# USB_CY7C68001-56LFC.net
KiCad netlist of a schematic drawn in Altium Designer
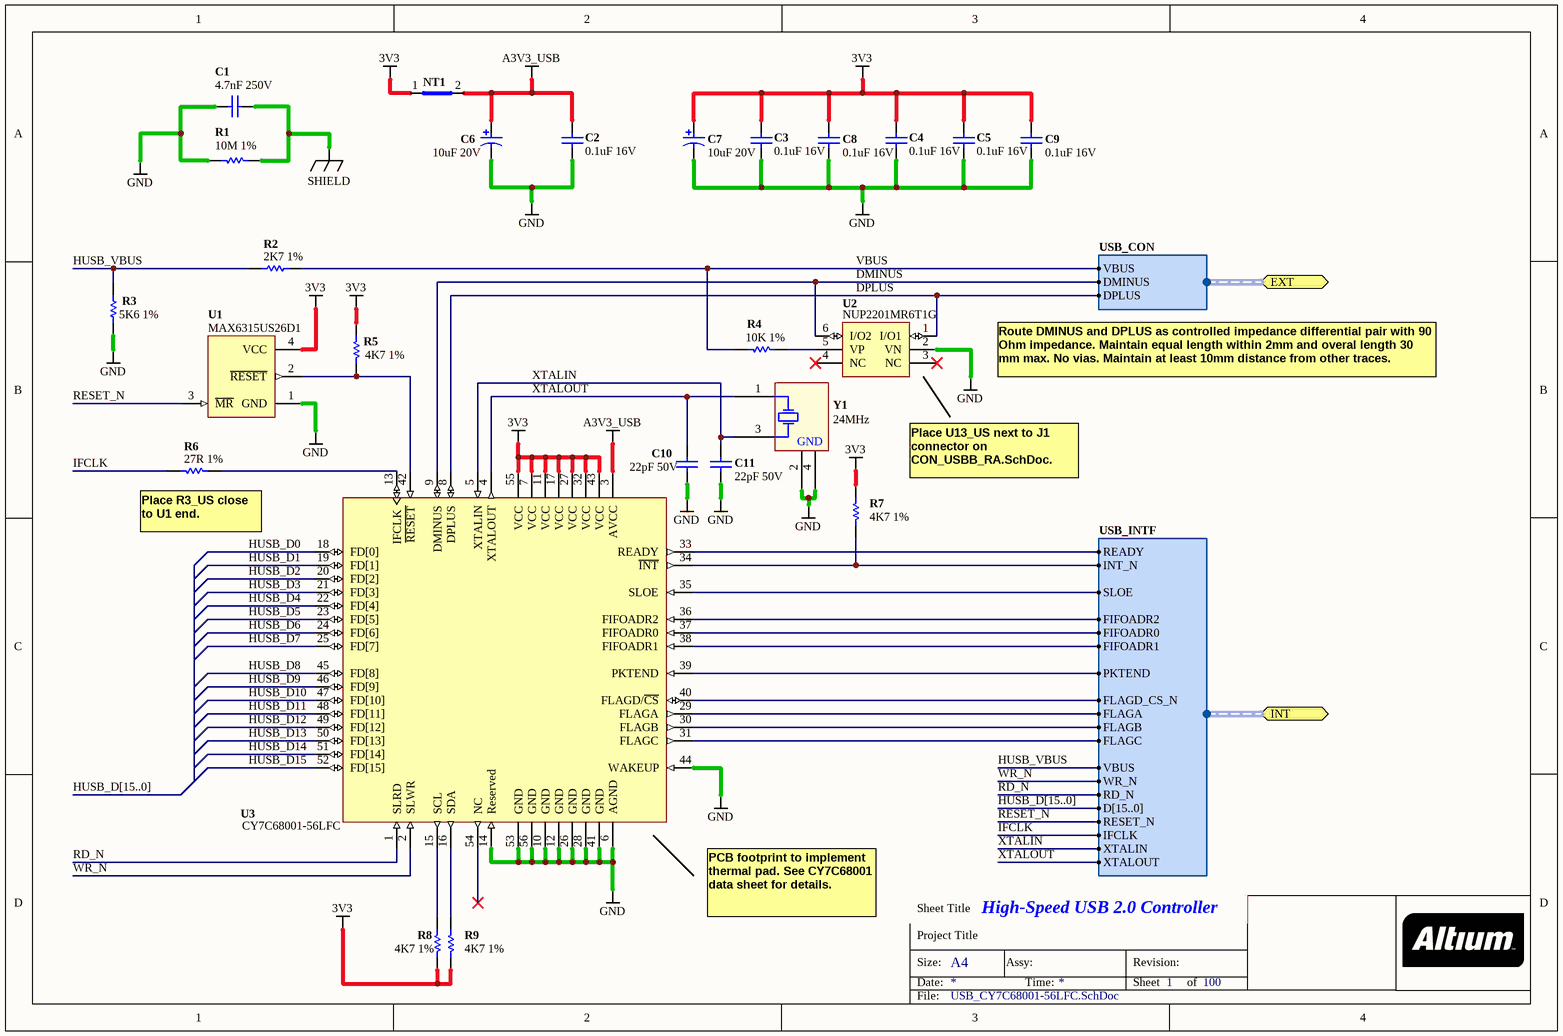
[diagram p0: USB_CY7C68001-56LFC.SchDoc]

(export (version "E")
  (design (tool "Eeschema 10.0.6"))
  (components
    (comp (ref "C1")
      (value "4.7nF 250V")
      (footprint "CAPM7163")
      (description "Capacitor, Ceramic, 4.7nF 20% 250V Panasonic BC J Lead (CAPM7163) Y5V")
      (fields (field (name "TOLERANCE") "20% %"))
      (libsource (lib "AltiumDesignLibrary") (part "CAP-NP"))
    )
    (comp (ref "C2")
      (value "0.1uF 16V")
      (footprint "CAPC1005-STAR")
      (description "Capacitor, Ceramic, 0.1uF 10% 16V 0402 (1005) X7R")
      (fields (field (name "TOLERANCE") "10 %"))
      (libsource (lib "AltiumDesignLibrary") (part "CAP-NP"))
    )
    (comp (ref "C3")
      (value "0.1uF 16V")
      (footprint "CAPC1005-STAR")
      (description "Capacitor, Ceramic, 0.1uF 10% 16V 0402 (1005) X7R")
      (fields (field (name "TOLERANCE") "10 %"))
      (libsource (lib "AltiumDesignLibrary") (part "CAP-NP"))
    )
    (comp (ref "C4")
      (value "0.1uF 16V")
      (footprint "CAPC1005-STAR")
      (description "Capacitor, Ceramic, 0.1uF 10% 16V 0402 (1005) X7R")
      (fields (field (name "TOLERANCE") "10 %"))
      (libsource (lib "AltiumDesignLibrary") (part "CAP-NP"))
    )
    (comp (ref "C5")
      (value "0.1uF 16V")
      (footprint "CAPC1005-STAR")
      (description "Capacitor, Ceramic, 0.1uF 10% 16V 0402 (1005) X7R")
      (fields (field (name "TOLERANCE") "10 %"))
      (libsource (lib "AltiumDesignLibrary") (part "CAP-NP"))
    )
    (comp (ref "C6")
      (value "10uF 20V")
      (footprint "CAPC3528-STAR")
      (description "Capacitor, Tantalum, 10uF 10% 20V MCCT-B (3528)")
      (fields (field (name "TOLERANCE") "10 %"))
      (libsource (lib "AltiumDesignLibrary") (part "CAP-P"))
    )
    (comp (ref "C7")
      (value "10uF 20V")
      (footprint "CAPC3528-STAR")
      (description "Capacitor, Tantalum, 10uF 10% 20V MCCT-B (3528)")
      (fields (field (name "TOLERANCE") "10 %"))
      (libsource (lib "AltiumDesignLibrary") (part "CAP-P"))
    )
    (comp (ref "C8")
      (value "0.1uF 16V")
      (footprint "CAPC1005-STAR")
      (description "Capacitor, Ceramic, 0.1uF 10% 16V 0402 (1005) X7R")
      (fields (field (name "TOLERANCE") "10 %"))
      (libsource (lib "AltiumDesignLibrary") (part "CAP-NP"))
    )
    (comp (ref "C9")
      (value "0.1uF 16V")
      (footprint "CAPC1005-STAR")
      (description "Capacitor, Ceramic, 0.1uF 10% 16V 0402 (1005) X7R")
      (fields (field (name "TOLERANCE") "10 %"))
      (libsource (lib "AltiumDesignLibrary") (part "CAP-NP"))
    )
    (comp (ref "C10")
      (value "22pF 50V")
      (footprint "CAPC1005-STAR")
      (description "Capacitor, Ceramic, 22pF 5% 50V 0402 (1005) COG")
      (fields (field (name "TOLERANCE") "5 %"))
      (libsource (lib "AltiumDesignLibrary") (part "CAP-NP"))
    )
    (comp (ref "C11")
      (value "22pF 50V")
      (footprint "CAPC1005-STAR")
      (description "Capacitor, Ceramic, 22pF 5% 50V 0402 (1005) COG")
      (fields (field (name "TOLERANCE") "5 %"))
      (libsource (lib "AltiumDesignLibrary") (part "CAP-NP"))
    )
    (comp (ref "NT1")
      (value "Net Tie SMT2")
      (footprint "NETTIE-SMT2-31X51")
      (description "Net-Tie, Surface Mount, 2 x 1.6mm x 0.8mm SMT Pads - For 0.8mm Track")
      (libsource (lib "AltiumDesignLibrary") (part "NETTIE-SMT2"))
    )
    (comp (ref "R1")
      (value "10M 1%")
      (footprint "RESC3216")
      (description "Resistor, 10M 1%1206 (3216)")
      (fields (field (name "TOLERANCE") "1 %"))
      (libsource (lib "AltiumDesignLibrary") (part "RES"))
    )
    (comp (ref "R2")
      (value "2K7 1%")
      (footprint "RESC1005-STAR")
      (description "Resistor, 2K7 1% 0402 (1005)")
      (fields (field (name "TOLERANCE") "1 %"))
      (libsource (lib "AltiumDesignLibrary") (part "RES"))
    )
    (comp (ref "R3")
      (value "5K6 1%")
      (footprint "RESC1005-STAR")
      (description "Resistor, 5K6 1% 0402 (1005)")
      (fields (field (name "TOLERANCE") "1 %"))
      (libsource (lib "AltiumDesignLibrary") (part "RES"))
    )
    (comp (ref "R4")
      (value "10K 1%")
      (footprint "RESC1005-STAR")
      (description "Resistor, 10K 1% 0402 (1005)")
      (fields (field (name "TOLERANCE") "1 %"))
      (libsource (lib "AltiumDesignLibrary") (part "RES"))
    )
    (comp (ref "R5")
      (value "4K7 1%")
      (footprint "RESC1005-STAR")
      (description "Resistor, 4K7 1% 0402 (1005)")
      (fields (field (name "TOLERANCE") "1 %"))
      (libsource (lib "AltiumDesignLibrary") (part "RES"))
    )
    (comp (ref "R6")
      (value "27R 1%")
      (footprint "RESC1005-STAR")
      (description "Resistor, 27R 1% 0402 (1005)")
      (fields (field (name "TOLERANCE") "1 %"))
      (libsource (lib "AltiumDesignLibrary") (part "RES"))
    )
    (comp (ref "R7")
      (value "4K7 1%")
      (footprint "RESC1005-STAR")
      (description "Resistor, 4K7 1% 0402 (1005)")
      (fields (field (name "TOLERANCE") "1 %"))
      (libsource (lib "AltiumDesignLibrary") (part "RES"))
    )
    (comp (ref "R8")
      (value "4K7 1%")
      (footprint "RESC1005-STAR")
      (description "Resistor, 4K7 1% 0402 (1005)")
      (fields (field (name "TOLERANCE") "1 %"))
      (libsource (lib "AltiumDesignLibrary") (part "RES"))
    )
    (comp (ref "R9")
      (value "4K7 1%")
      (footprint "RESC1005-STAR")
      (description "Resistor, 4K7 1% 0402 (1005)")
      (fields (field (name "TOLERANCE") "1 %"))
      (libsource (lib "AltiumDesignLibrary") (part "RES"))
    )
    (comp (ref "U1")
      (value "MAX6315US26D1")
      (footprint "SOT143")
      (description "MAX6315, Open-Drain Output SOT Reset IC, Customized Reset Thresholds, Timeout Delays")
      (libsource (lib "AltiumDesignLibrary") (part "MAX6315"))
    )
    (comp (ref "U2")
      (value "NUP2201MR6T1G")
      (footprint "TSOP95P275-6")
      (description "NUP2201MR6, Low Capacitance Diode Array, USB Protection")
      (libsource (lib "AltiumDesignLibrary") (part "NUP2201MR6"))
    )
    (comp (ref "U3")
      (value "CY7C68001-56LFC")
      (footprint "QFN50P800X800_HS-57")
      (description "CY7C68001-56LFC, EZ-USB SX2 High-Speed USB Interface")
      (libsource (lib "AltiumDesignLibrary") (part "CY7C68001-56LFC"))
    )
    (comp (ref "Y1")
      (value "24MHz")
      (footprint "XTAL-200X126-4")
      (description "Crystal, SMD, 24.000000MHz Stab=30ppm 20.0pF")
      (libsource (lib "AltiumDesignLibrary") (part "CRYSTAL-200X126-4"))
    )
  )
  (nets
    (net (code "3") (name "/DMINUS") (class "Default")
      (node (ref "U2") (pin "6") (pinfunction "I/O2_6") (pintype "bidirectional"))
      (node (ref "U3") (pin "9") (pinfunction "DMINUS_9") (pintype "bidirectional"))
    )
    (net (code "4") (name "/DPLUS") (class "Default")
      (node (ref "U2") (pin "1") (pinfunction "I/O1_1") (pintype "bidirectional"))
      (node (ref "U3") (pin "8") (pinfunction "DPLUS_8") (pintype "bidirectional"))
    )
    (net (code "5") (name "/FIFOADR0") (class "Default")
      (node (ref "U3") (pin "37") (pinfunction "FIFOADR0_37") (pintype "input"))
    )
    (net (code "6") (name "/FIFOADR1") (class "Default")
      (node (ref "U3") (pin "38") (pinfunction "FIFOADR1_38") (pintype "input"))
    )
    (net (code "7") (name "/FIFOADR2") (class "Default")
      (node (ref "U3") (pin "36") (pinfunction "FIFOADR2_36") (pintype "input"))
    )
    (net (code "8") (name "/FLAGA") (class "Default")
      (node (ref "U3") (pin "29") (pinfunction "FLAGA_29") (pintype "output"))
    )
    (net (code "9") (name "/FLAGB") (class "Default")
      (node (ref "U3") (pin "30") (pinfunction "FLAGB_30") (pintype "output"))
    )
    (net (code "10") (name "/FLAGC") (class "Default")
      (node (ref "U3") (pin "31") (pinfunction "FLAGC_31") (pintype "output"))
    )
    (net (code "11") (name "/FLAGD_CS_N") (class "Default")
      (node (ref "U3") (pin "40") (pinfunction "FLAGD/~{CS}_40") (pintype "bidirectional"))
    )
    (net (code "12") (name "/HUSB_D0") (class "Default")
      (node (ref "U3") (pin "18") (pinfunction "FD[0]_18") (pintype "bidirectional"))
    )
    (net (code "13") (name "/HUSB_D1") (class "Default")
      (node (ref "U3") (pin "19") (pinfunction "FD[1]_19") (pintype "bidirectional"))
    )
    (net (code "14") (name "/HUSB_D2") (class "Default")
      (node (ref "U3") (pin "20") (pinfunction "FD[2]_20") (pintype "bidirectional"))
    )
    (net (code "15") (name "/HUSB_D3") (class "Default")
      (node (ref "U3") (pin "21") (pinfunction "FD[3]_21") (pintype "bidirectional"))
    )
    (net (code "16") (name "/HUSB_D4") (class "Default")
      (node (ref "U3") (pin "22") (pinfunction "FD[4]_22") (pintype "bidirectional"))
    )
    (net (code "17") (name "/HUSB_D5") (class "Default")
      (node (ref "U3") (pin "23") (pinfunction "FD[5]_23") (pintype "bidirectional"))
    )
    (net (code "18") (name "/HUSB_D6") (class "Default")
      (node (ref "U3") (pin "24") (pinfunction "FD[6]_24") (pintype "bidirectional"))
    )
    (net (code "19") (name "/HUSB_D7") (class "Default")
      (node (ref "U3") (pin "25") (pinfunction "FD[7]_25") (pintype "bidirectional"))
    )
    (net (code "20") (name "/HUSB_D8") (class "Default")
      (node (ref "U3") (pin "45") (pinfunction "FD[8]_45") (pintype "bidirectional"))
    )
    (net (code "21") (name "/HUSB_D9") (class "Default")
      (node (ref "U3") (pin "46") (pinfunction "FD[9]_46") (pintype "bidirectional"))
    )
    (net (code "22") (name "/HUSB_D10") (class "Default")
      (node (ref "U3") (pin "47") (pinfunction "FD[10]_47") (pintype "bidirectional"))
    )
    (net (code "23") (name "/HUSB_D11") (class "Default")
      (node (ref "U3") (pin "48") (pinfunction "FD[11]_48") (pintype "bidirectional"))
    )
    (net (code "24") (name "/HUSB_D12") (class "Default")
      (node (ref "U3") (pin "49") (pinfunction "FD[12]_49") (pintype "bidirectional"))
    )
    (net (code "25") (name "/HUSB_D13") (class "Default")
      (node (ref "U3") (pin "50") (pinfunction "FD[13]_50") (pintype "bidirectional"))
    )
    (net (code "26") (name "/HUSB_D14") (class "Default")
      (node (ref "U3") (pin "51") (pinfunction "FD[14]_51") (pintype "bidirectional"))
    )
    (net (code "27") (name "/HUSB_D15") (class "Default")
      (node (ref "U3") (pin "52") (pinfunction "FD[15]_52") (pintype "bidirectional"))
    )
    (net (code "29") (name "/HUSB_VBUS") (class "Default")
      (node (ref "R2") (pin "1") (pinfunction "1_1") (pintype "passive"))
      (node (ref "R3") (pin "1") (pinfunction "1_1") (pintype "passive"))
    )
    (net (code "30") (name "/IFCLK") (class "Default")
      (node (ref "R6") (pin "1") (pinfunction "1_1") (pintype "passive"))
    )
    (net (code "31") (name "/INT_N") (class "Default")
      (node (ref "R7") (pin "1") (pinfunction "1_1") (pintype "passive"))
      (node (ref "U3") (pin "34") (pinfunction "~{INT}_34") (pintype "output"))
    )
    (net (code "32") (name "/PKTEND") (class "Default")
      (node (ref "U3") (pin "39") (pinfunction "PKTEND_39") (pintype "input"))
    )
    (net (code "33") (name "/RD_N") (class "Default")
      (node (ref "U3") (pin "1") (pinfunction "SLRD_1") (pintype "input"))
    )
    (net (code "34") (name "/READY") (class "Default")
      (node (ref "U3") (pin "33") (pinfunction "READY_33") (pintype "output"))
    )
    (net (code "35") (name "/RESET_N") (class "Default")
      (node (ref "U1") (pin "3") (pinfunction "~{MR}_3") (pintype "input"))
    )
    (net (code "36") (name "/SLOE") (class "Default")
      (node (ref "U3") (pin "35") (pinfunction "SLOE_35") (pintype "input"))
    )
    (net (code "37") (name "/VBUS") (class "Default")
      (node (ref "R2") (pin "2") (pinfunction "2_2") (pintype "passive"))
      (node (ref "R4") (pin "1") (pinfunction "1_1") (pintype "passive"))
    )
    (net (code "38") (name "/WR_N") (class "Default")
      (node (ref "U3") (pin "2") (pinfunction "SLWR_2") (pintype "input"))
    )
    (net (code "39") (name "/XTALIN") (class "Default")
      (node (ref "C11") (pin "1") (pinfunction "1_1") (pintype "passive"))
      (node (ref "U3") (pin "5") (pinfunction "XTALIN_5") (pintype "input"))
      (node (ref "Y1") (pin "3") (pinfunction "X2_3") (pintype "passive"))
    )
    (net (code "40") (name "/XTALOUT") (class "Default")
      (node (ref "C10") (pin "1") (pinfunction "1_1") (pintype "passive"))
      (node (ref "U3") (pin "4") (pinfunction "XTALOUT_4") (pintype "output"))
      (node (ref "Y1") (pin "1") (pinfunction "X1_1") (pintype "passive"))
    )
    (net (code "43") (name "3V3") (class "Default")
      (node (ref "C3") (pin "2") (pinfunction "2_2") (pintype "passive"))
      (node (ref "C4") (pin "2") (pinfunction "2_2") (pintype "passive"))
      (node (ref "C5") (pin "2") (pinfunction "2_2") (pintype "passive"))
      (node (ref "C7") (pin "1") (pinfunction "1_1") (pintype "passive"))
      (node (ref "C8") (pin "1") (pinfunction "1_1") (pintype "passive"))
      (node (ref "C9") (pin "1") (pinfunction "1_1") (pintype "passive"))
      (node (ref "NT1") (pin "1") (pinfunction "Net1_1") (pintype "passive"))
      (node (ref "R5") (pin "2") (pinfunction "2_2") (pintype "passive"))
      (node (ref "R7") (pin "2") (pinfunction "2_2") (pintype "passive"))
      (node (ref "R8") (pin "1") (pinfunction "1_1") (pintype "passive"))
      (node (ref "R9") (pin "1") (pinfunction "1_1") (pintype "passive"))
      (node (ref "U1") (pin "4") (pinfunction "VCC_4") (pintype "power_in"))
      (node (ref "U3") (pin "11") (pinfunction "VCC_11") (pintype "power_in"))
      (node (ref "U3") (pin "17") (pinfunction "VCC_17") (pintype "power_in"))
      (node (ref "U3") (pin "27") (pinfunction "VCC_27") (pintype "power_in"))
      (node (ref "U3") (pin "32") (pinfunction "VCC_32") (pintype "power_in"))
      (node (ref "U3") (pin "43") (pinfunction "VCC_43") (pintype "power_in"))
      (node (ref "U3") (pin "55") (pinfunction "VCC_55") (pintype "power_in"))
      (node (ref "U3") (pin "7") (pinfunction "VCC_7") (pintype "power_in"))
    )
    (net (code "44") (name "A3V3_USB") (class "Default")
      (node (ref "C2") (pin "2") (pinfunction "2_2") (pintype "passive"))
      (node (ref "C6") (pin "1") (pinfunction "1_1") (pintype "passive"))
      (node (ref "NT1") (pin "2") (pinfunction "Net2_2") (pintype "passive"))
      (node (ref "U3") (pin "3") (pinfunction "AVCC_3") (pintype "power_in"))
    )
    (net (code "45") (name "GND") (class "Default")
      (node (ref "C1") (pin "2") (pinfunction "2_2") (pintype "passive"))
      (node (ref "C10") (pin "2") (pinfunction "2_2") (pintype "passive"))
      (node (ref "C11") (pin "2") (pinfunction "2_2") (pintype "passive"))
      (node (ref "C2") (pin "1") (pinfunction "1_1") (pintype "passive"))
      (node (ref "C3") (pin "1") (pinfunction "1_1") (pintype "passive"))
      (node (ref "C4") (pin "1") (pinfunction "1_1") (pintype "passive"))
      (node (ref "C5") (pin "1") (pinfunction "1_1") (pintype "passive"))
      (node (ref "C6") (pin "2") (pinfunction "2_2") (pintype "passive"))
      (node (ref "C7") (pin "2") (pinfunction "2_2") (pintype "passive"))
      (node (ref "C8") (pin "2") (pinfunction "2_2") (pintype "passive"))
      (node (ref "C9") (pin "2") (pinfunction "2_2") (pintype "passive"))
      (node (ref "R1") (pin "2") (pinfunction "2_2") (pintype "passive"))
      (node (ref "R3") (pin "2") (pinfunction "2_2") (pintype "passive"))
      (node (ref "U1") (pin "1") (pinfunction "GND_1") (pintype "power_in"))
      (node (ref "U2") (pin "2") (pinfunction "VN_2") (pintype "power_in"))
      (node (ref "U3") (pin "10") (pinfunction "GND_10") (pintype "power_in"))
      (node (ref "U3") (pin "12") (pinfunction "GND_12") (pintype "power_in"))
      (node (ref "U3") (pin "14") (pinfunction "Reserved_14") (pintype "input"))
      (node (ref "U3") (pin "26") (pinfunction "GND_26") (pintype "power_in"))
      (node (ref "U3") (pin "28") (pinfunction "GND_28") (pintype "power_in"))
      (node (ref "U3") (pin "41") (pinfunction "GND_41") (pintype "power_in"))
      (node (ref "U3") (pin "44") (pinfunction "WAKEUP_44") (pintype "input"))
      (node (ref "U3") (pin "53") (pinfunction "GND_53") (pintype "power_in"))
      (node (ref "U3") (pin "56") (pinfunction "GND_56") (pintype "power_in"))
      (node (ref "U3") (pin "6") (pinfunction "AGND_6") (pintype "power_in"))
      (node (ref "Y1") (pin "2") (pinfunction "GND_2") (pintype "passive"))
      (node (ref "Y1") (pin "4") (pinfunction "GND_4") (pintype "passive"))
    )
    (net (code "46") (name "Net-(U1-~{RESET})") (class "Default")
      (node (ref "R5") (pin "1") (pinfunction "1_1") (pintype "passive"))
      (node (ref "U1") (pin "2") (pinfunction "~{RESET}_2") (pintype "output"))
      (node (ref "U3") (pin "42") (pinfunction "~{RESET}_42") (pintype "input"))
    )
    (net (code "47") (name "Net-(U2-VP)") (class "Default")
      (node (ref "R4") (pin "2") (pinfunction "2_2") (pintype "passive"))
      (node (ref "U2") (pin "5") (pinfunction "VP_5") (pintype "power_in"))
    )
    (net (code "48") (name "Net-(U3-IFCLK)") (class "Default")
      (node (ref "R6") (pin "2") (pinfunction "2_2") (pintype "passive"))
      (node (ref "U3") (pin "13") (pinfunction "IFCLK_13") (pintype "bidirectional"))
    )
    (net (code "49") (name "Net-(U3-SCL)") (class "Default")
      (node (ref "R8") (pin "2") (pinfunction "2_2") (pintype "passive"))
      (node (ref "U3") (pin "15") (pinfunction "SCL_15") (pintype "output"))
    )
    (net (code "50") (name "Net-(U3-SDA)") (class "Default")
      (node (ref "R9") (pin "2") (pinfunction "2_2") (pintype "passive"))
      (node (ref "U3") (pin "16") (pinfunction "SDA_16") (pintype "output"))
    )
    (net (code "51") (name "SHIELD") (class "Default")
      (node (ref "C1") (pin "1") (pinfunction "1_1") (pintype "passive"))
      (node (ref "R1") (pin "1") (pinfunction "1_1") (pintype "passive"))
    )
    (net (code "52") (name "unconnected-(U2-NC-Pad3)") (class "Default")
      (node (ref "U2") (pin "3") (pinfunction "NC_3") (pintype "passive+no_connect"))
    )
    (net (code "53") (name "unconnected-(U2-NC-Pad4)") (class "Default")
      (node (ref "U2") (pin "4") (pinfunction "NC_4") (pintype "passive+no_connect"))
    )
    (net (code "54") (name "unconnected-(U3-NC-Pad54)") (class "Default")
      (node (ref "U3") (pin "54") (pinfunction "NC_54") (pintype "output+no_connect"))
    )
  )
)
